# Balanbot-v2_0.net
KiCad netlist of a schematic drawn in EAGLE
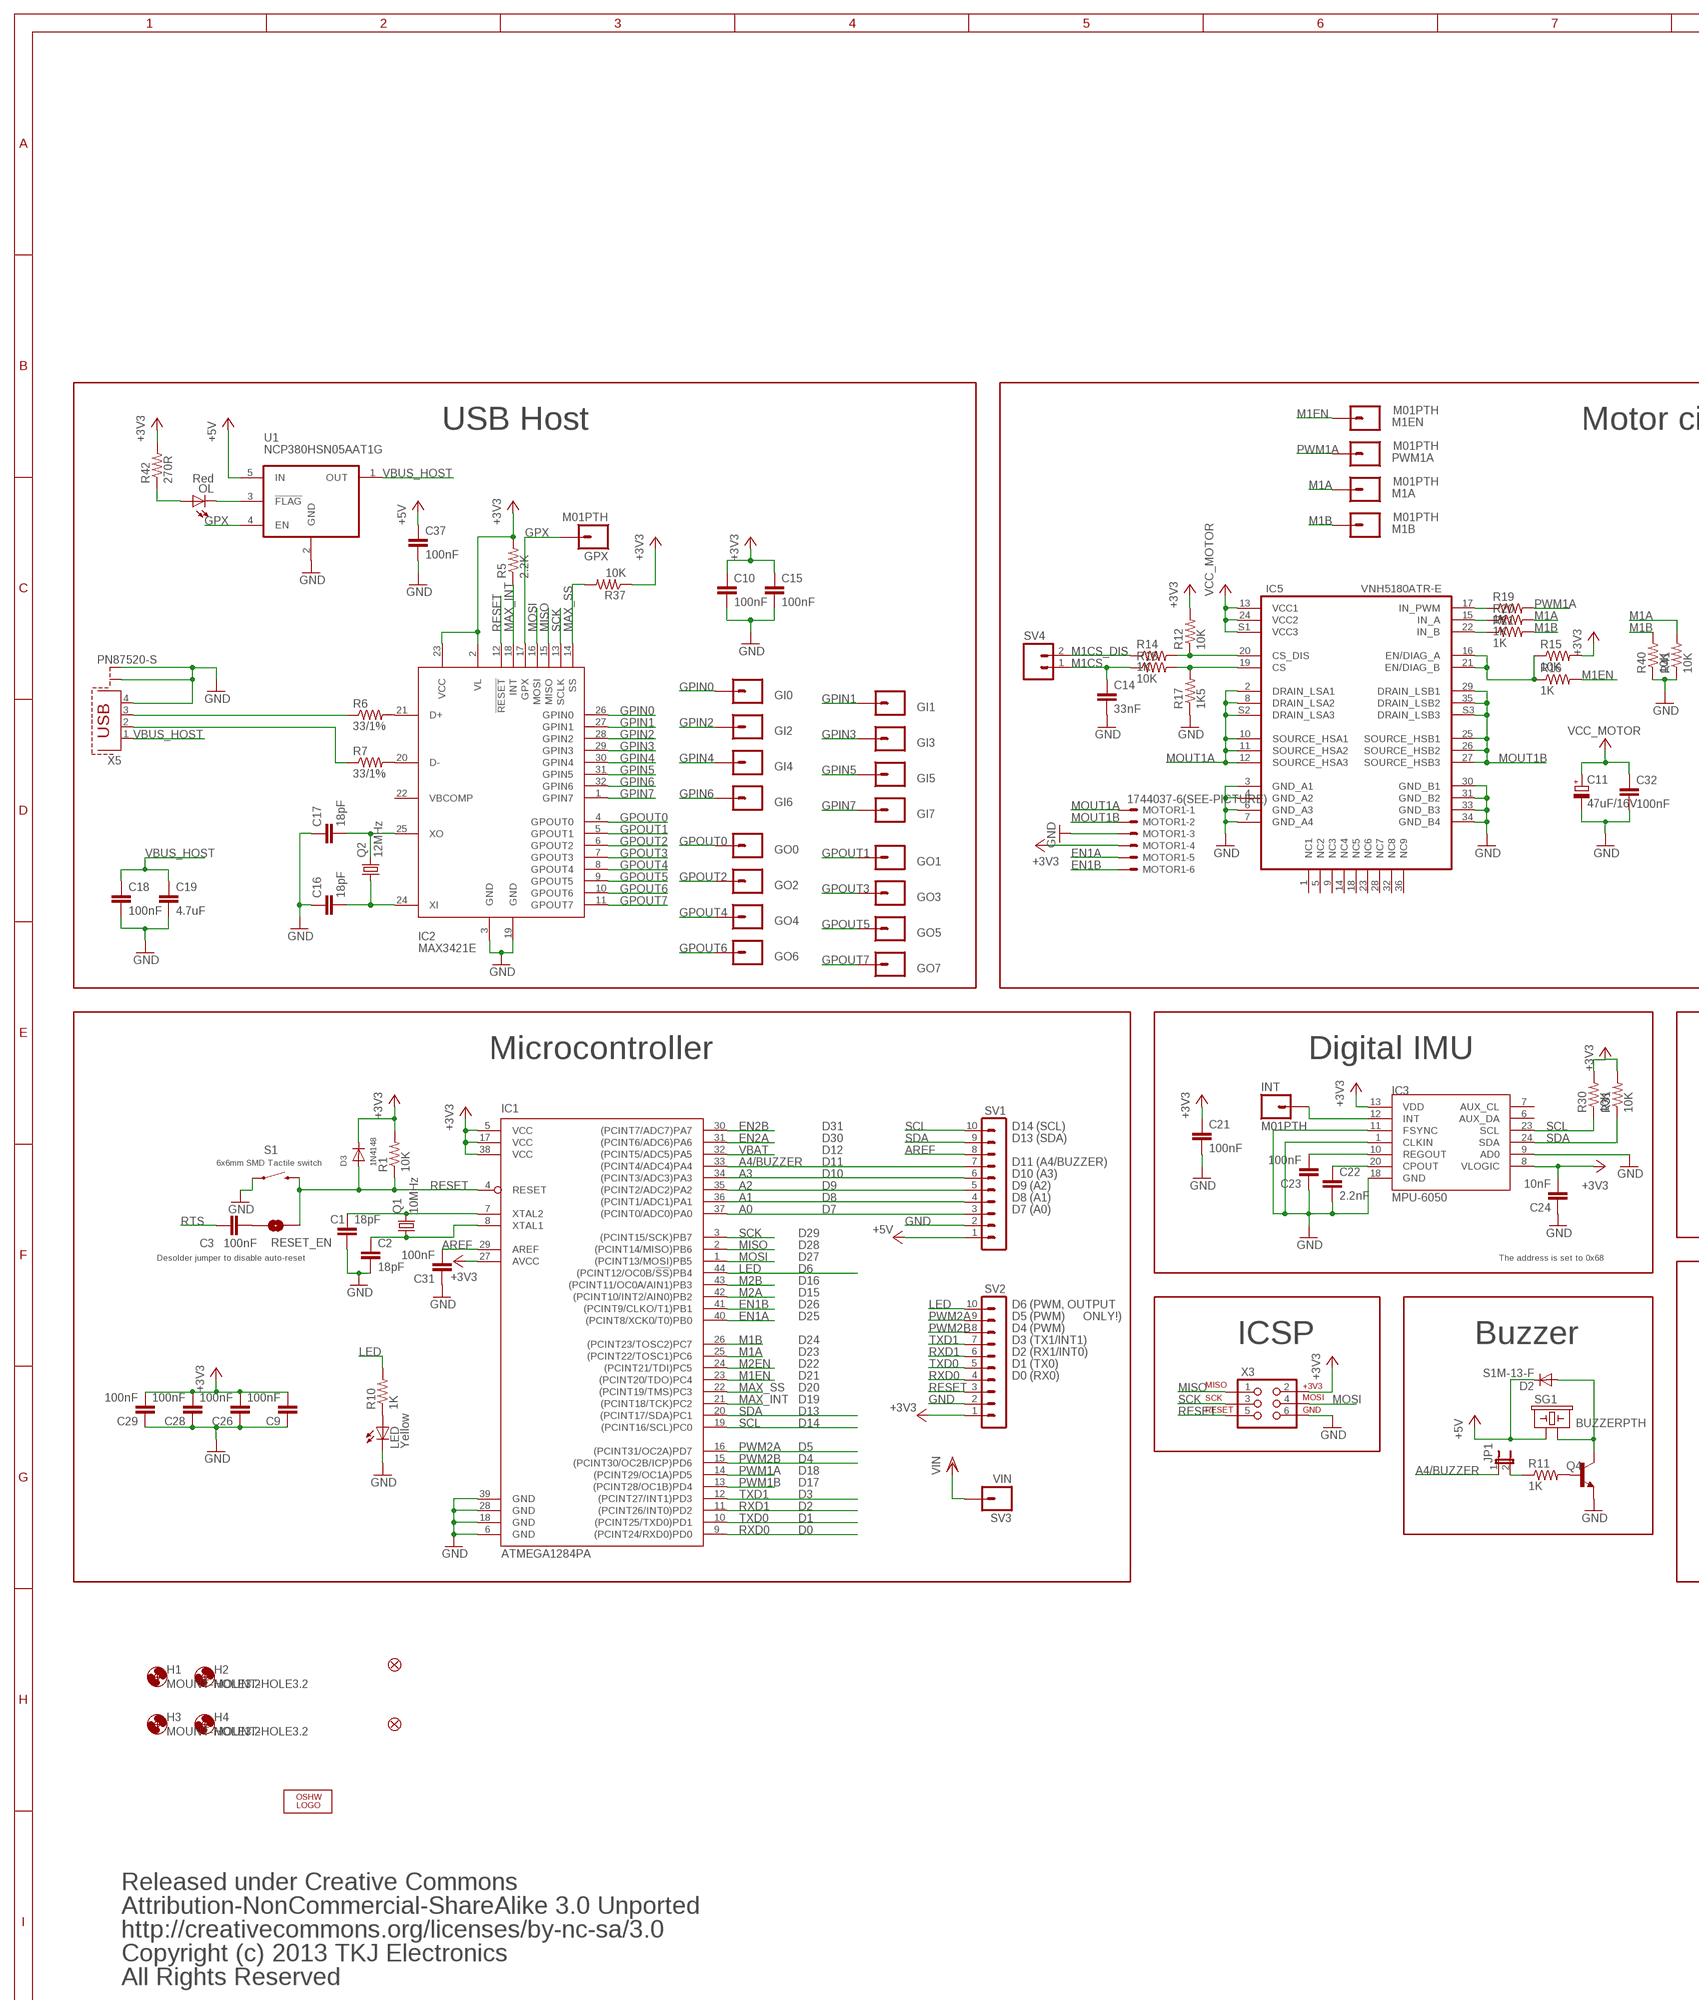
[diagram p0: schematic, sheet 1, part 1 of 2]
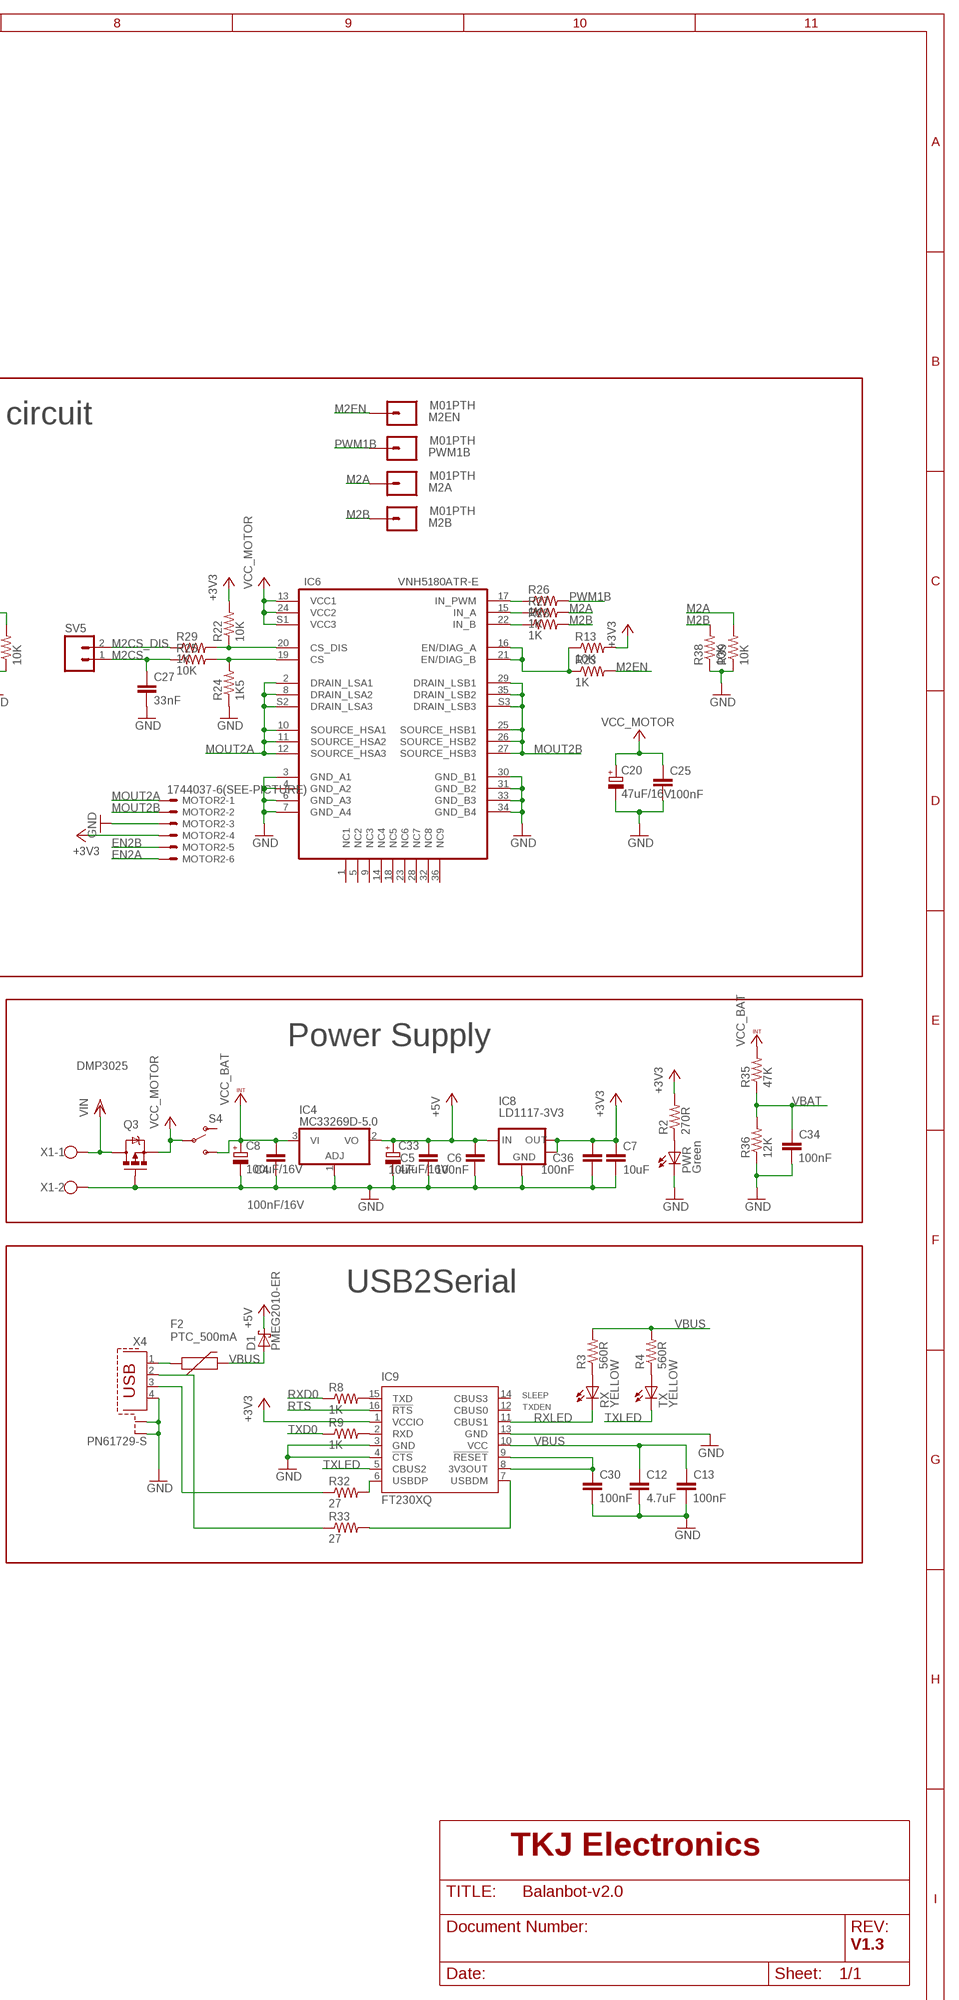
[diagram p1: schematic, sheet 1, part 2 of 2]

(export (version "E")
  (design (tool "Eeschema 10.0.6"))
  (components
    (comp (ref "C1")
      (value "18pF")
      (footprint "eagle-import:C0603")
      (libsource (lib "eagle-import") (part "C-EUC0603"))
    )
    (comp (ref "C2")
      (value "18pF")
      (footprint "eagle-import:C0603")
      (libsource (lib "eagle-import") (part "C-EUC0603"))
    )
    (comp (ref "C3")
      (value "100nF")
      (footprint "eagle-import:C0603")
      (libsource (lib "eagle-import") (part "C-EUC0603"))
    )
    (comp (ref "C4")
      (value "100nF/16V")
      (footprint "eagle-import:C0603")
      (libsource (lib "eagle-import") (part "C-EUC0603"))
    )
    (comp (ref "C5")
      (value "10uF")
      (footprint "eagle-import:C0805")
      (libsource (lib "eagle-import") (part "C-EUC0805"))
    )
    (comp (ref "C6")
      (value "100nF")
      (footprint "eagle-import:C0603")
      (libsource (lib "eagle-import") (part "C-EUC0603"))
    )
    (comp (ref "C7")
      (value "10uF")
      (footprint "eagle-import:C0805")
      (libsource (lib "eagle-import") (part "C-EUC0805"))
    )
    (comp (ref "C8")
      (value "100uF/16V")
      (footprint "eagle-import:PANASONIC_D")
      (libsource (lib "eagle-import") (part "CPOL-EUD"))
    )
    (comp (ref "C9")
      (value "100nF")
      (footprint "eagle-import:C0603")
      (libsource (lib "eagle-import") (part "C-EUC0603"))
    )
    (comp (ref "C10")
      (value "100nF")
      (footprint "eagle-import:C0603")
      (libsource (lib "eagle-import") (part "C-EUC0603"))
    )
    (comp (ref "C11")
      (value "47uF/16V")
      (footprint "eagle-import:PANASONIC_C")
      (libsource (lib "eagle-import") (part "CPOL-EUC"))
    )
    (comp (ref "C12")
      (value "4.7uF")
      (footprint "eagle-import:C0805")
      (libsource (lib "eagle-import") (part "C-EUC0805"))
    )
    (comp (ref "C13")
      (value "100nF")
      (footprint "eagle-import:C0603")
      (libsource (lib "eagle-import") (part "C-EUC0603"))
    )
    (comp (ref "C14")
      (value "33nF")
      (footprint "eagle-import:C0603")
      (libsource (lib "eagle-import") (part "C-EUC0603"))
    )
    (comp (ref "C15")
      (value "100nF")
      (footprint "eagle-import:C0603")
      (libsource (lib "eagle-import") (part "C-EUC0603"))
    )
    (comp (ref "C16")
      (value "18pF")
      (footprint "eagle-import:C0603")
      (libsource (lib "eagle-import") (part "C-EUC0603"))
    )
    (comp (ref "C17")
      (value "18pF")
      (footprint "eagle-import:C0603")
      (libsource (lib "eagle-import") (part "C-EUC0603"))
    )
    (comp (ref "C18")
      (value "100nF")
      (footprint "eagle-import:C0603")
      (libsource (lib "eagle-import") (part "C-EUC0603"))
    )
    (comp (ref "C19")
      (value "4.7uF")
      (footprint "eagle-import:C0805")
      (libsource (lib "eagle-import") (part "C-EUC0805"))
    )
    (comp (ref "C20")
      (value "47uF/16V")
      (footprint "eagle-import:PANASONIC_C")
      (libsource (lib "eagle-import") (part "CPOL-EUC"))
    )
    (comp (ref "C21")
      (value "100nF")
      (footprint "eagle-import:C0603")
      (libsource (lib "eagle-import") (part "C-EUC0603"))
    )
    (comp (ref "C22")
      (value "2.2nF")
      (footprint "eagle-import:C0603")
      (libsource (lib "eagle-import") (part "C-EUC0603"))
    )
    (comp (ref "C23")
      (value "100nF")
      (footprint "eagle-import:C0603")
      (libsource (lib "eagle-import") (part "C-EUC0603"))
    )
    (comp (ref "C24")
      (value "10nF")
      (footprint "eagle-import:C0603")
      (libsource (lib "eagle-import") (part "C-EUC0603"))
    )
    (comp (ref "C25")
      (value "100nF")
      (footprint "eagle-import:C0603")
      (libsource (lib "eagle-import") (part "C-EUC0603"))
    )
    (comp (ref "C26")
      (value "100nF")
      (footprint "eagle-import:C0603")
      (libsource (lib "eagle-import") (part "C-EUC0603"))
    )
    (comp (ref "C27")
      (value "33nF")
      (footprint "eagle-import:C0603")
      (libsource (lib "eagle-import") (part "C-EUC0603"))
    )
    (comp (ref "C28")
      (value "100nF")
      (footprint "eagle-import:C0603")
      (libsource (lib "eagle-import") (part "C-EUC0603"))
    )
    (comp (ref "C29")
      (value "100nF")
      (footprint "eagle-import:C0603")
      (libsource (lib "eagle-import") (part "C-EUC0603"))
    )
    (comp (ref "C30")
      (value "100nF")
      (footprint "eagle-import:C0603")
      (libsource (lib "eagle-import") (part "C-EUC0603"))
    )
    (comp (ref "C31")
      (value "100nF")
      (footprint "eagle-import:C0603")
      (libsource (lib "eagle-import") (part "C-EUC0603"))
    )
    (comp (ref "C32")
      (value "100nF")
      (footprint "eagle-import:C0603")
      (libsource (lib "eagle-import") (part "C-EUC0603"))
    )
    (comp (ref "C33")
      (value "47uF/16V")
      (footprint "eagle-import:PANASONIC_C")
      (libsource (lib "eagle-import") (part "CPOL-EUC"))
    )
    (comp (ref "C34")
      (value "100nF")
      (footprint "eagle-import:C0603")
      (libsource (lib "eagle-import") (part "C-EUC0603"))
    )
    (comp (ref "C36")
      (value "100nF")
      (footprint "eagle-import:C0603")
      (libsource (lib "eagle-import") (part "C-EUC0603"))
    )
    (comp (ref "C37")
      (value "100nF")
      (footprint "eagle-import:C0603")
      (libsource (lib "eagle-import") (part "C-EUC0603"))
    )
    (comp (ref "D1")
      (value "PMEG2010-ER")
      (footprint "eagle-import:SOD123")
      (libsource (lib "eagle-import") (part "PMEG2010-ER"))
    )
    (comp (ref "D2")
      (value "S1M-13-F")
      (footprint "eagle-import:DO214AC")
      (libsource (lib "eagle-import") (part "S1M-13-F"))
    )
    (comp (ref "D3")
      (value "1N4148")
      (footprint "eagle-import:SOD-523")
      (libsource (lib "eagle-import") (part "DIODESOD-523"))
    )
    (comp (ref "F2")
      (value "PTC_500mA")
      (footprint "eagle-import:PTC-1206")
      (libsource (lib "eagle-import") (part "PTCSMD"))
    )
    (comp (ref "GI0")
      (value "M01PTH")
      (footprint "eagle-import:1X01")
      (libsource (lib "eagle-import") (part "M01PTH"))
    )
    (comp (ref "GI1")
      (value "M01PTH")
      (footprint "eagle-import:1X01")
      (libsource (lib "eagle-import") (part "M01PTH"))
    )
    (comp (ref "GI2")
      (value "M01PTH")
      (footprint "eagle-import:1X01")
      (libsource (lib "eagle-import") (part "M01PTH"))
    )
    (comp (ref "GI3")
      (value "M01PTH")
      (footprint "eagle-import:1X01")
      (libsource (lib "eagle-import") (part "M01PTH"))
    )
    (comp (ref "GI4")
      (value "M01PTH")
      (footprint "eagle-import:1X01")
      (libsource (lib "eagle-import") (part "M01PTH"))
    )
    (comp (ref "GI5")
      (value "M01PTH")
      (footprint "eagle-import:1X01")
      (libsource (lib "eagle-import") (part "M01PTH"))
    )
    (comp (ref "GI6")
      (value "M01PTH")
      (footprint "eagle-import:1X01")
      (libsource (lib "eagle-import") (part "M01PTH"))
    )
    (comp (ref "GI7")
      (value "M01PTH")
      (footprint "eagle-import:1X01")
      (libsource (lib "eagle-import") (part "M01PTH"))
    )
    (comp (ref "GO0")
      (value "M01PTH")
      (footprint "eagle-import:1X01")
      (libsource (lib "eagle-import") (part "M01PTH"))
    )
    (comp (ref "GO1")
      (value "M01PTH")
      (footprint "eagle-import:1X01")
      (libsource (lib "eagle-import") (part "M01PTH"))
    )
    (comp (ref "GO2")
      (value "M01PTH")
      (footprint "eagle-import:1X01")
      (libsource (lib "eagle-import") (part "M01PTH"))
    )
    (comp (ref "GO3")
      (value "M01PTH")
      (footprint "eagle-import:1X01")
      (libsource (lib "eagle-import") (part "M01PTH"))
    )
    (comp (ref "GO4")
      (value "M01PTH")
      (footprint "eagle-import:1X01")
      (libsource (lib "eagle-import") (part "M01PTH"))
    )
    (comp (ref "GO5")
      (value "M01PTH")
      (footprint "eagle-import:1X01")
      (libsource (lib "eagle-import") (part "M01PTH"))
    )
    (comp (ref "GO6")
      (value "M01PTH")
      (footprint "eagle-import:1X01")
      (libsource (lib "eagle-import") (part "M01PTH"))
    )
    (comp (ref "GO7")
      (value "M01PTH")
      (footprint "eagle-import:1X01")
      (libsource (lib "eagle-import") (part "M01PTH"))
    )
    (comp (ref "GPX")
      (value "M01PTH")
      (footprint "eagle-import:1X01")
      (libsource (lib "eagle-import") (part "M01PTH"))
    )
    (comp (ref "H1")
      (value "MOUNT-HOLE3.2")
      (footprint "eagle-import:3,2")
      (libsource (lib "eagle-import") (part "MOUNT-HOLE3.2"))
    )
    (comp (ref "H2")
      (value "MOUNT-HOLE3.2")
      (footprint "eagle-import:3,2")
      (libsource (lib "eagle-import") (part "MOUNT-HOLE3.2"))
    )
    (comp (ref "H3")
      (value "MOUNT-HOLE3.2")
      (footprint "eagle-import:3,2")
      (libsource (lib "eagle-import") (part "MOUNT-HOLE3.2"))
    )
    (comp (ref "H4")
      (value "MOUNT-HOLE3.2")
      (footprint "eagle-import:3,2")
      (libsource (lib "eagle-import") (part "MOUNT-HOLE3.2"))
    )
    (comp (ref "IC1")
      (value "ATMEGA1284PA")
      (footprint "eagle-import:TQFP44")
      (fields (field (name "MPN") "ATMEGA1284P-10AU"))
      (libsource (lib "eagle-import") (part "ATMEGA1284PA"))
    )
    (comp (ref "IC2")
      (value "MAX3421E")
      (footprint "eagle-import:TQFP32_8MIL")
      (libsource (lib "eagle-import") (part "MAX3421E"))
    )
    (comp (ref "IC3")
      (value "MPU-6050")
      (footprint "eagle-import:TESTING_QFN-24-4MM2")
      (libsource (lib "eagle-import") (part "TESTING_MPU-6050-1"))
    )
    (comp (ref "IC4")
      (value "MC33269D-5.0")
      (footprint "eagle-import:DPACK")
      (libsource (lib "eagle-import") (part "MC33269?D"))
    )
    (comp (ref "IC5")
      (value "VNH5180ATR-E")
      (footprint "eagle-import:POWERSSO-36")
      (libsource (lib "eagle-import") (part "VNH5180ATR-E"))
    )
    (comp (ref "IC6")
      (value "VNH5180ATR-E")
      (footprint "eagle-import:POWERSSO-36")
      (libsource (lib "eagle-import") (part "VNH5180ATR-E"))
    )
    (comp (ref "IC8")
      (value "LD1117-3V3")
      (footprint "eagle-import:SOT223")
      (libsource (lib "eagle-import") (part "LM1117-SOT223"))
    )
    (comp (ref "IC9")
      (value "FT230XQ")
      (footprint "eagle-import:QFN16")
      (libsource (lib "eagle-import") (part "FT230XQ"))
    )
    (comp (ref "INT")
      (value "M01PTH")
      (footprint "eagle-import:1X01")
      (libsource (lib "eagle-import") (part "M01PTH"))
    )
    (comp (ref "JP1")
      (value "JP1E")
      (footprint "eagle-import:JP1")
      (libsource (lib "eagle-import") (part "JP1E"))
    )
    (comp (ref "JP2")
      (value "FIDUCIALUFIDUCIAL")
      (footprint "eagle-import:MICRO-FIDUCIAL")
      (libsource (lib "eagle-import") (part "FIDUCIALUFIDUCIAL"))
    )
    (comp (ref "JP3")
      (value "FIDUCIAL1X2")
      (footprint "eagle-import:FIDUCIAL-1X2")
      (libsource (lib "eagle-import") (part "FIDUCIAL1X2"))
    )
    (comp (ref "LED")
      (value "Yellow")
      (footprint "eagle-import:CHIPLED_0805")
      (libsource (lib "eagle-import") (part "LEDCHIPLED_0805"))
    )
    (comp (ref "LOGO2")
      (value "OSHW_LOGO_FILLX0200-NT")
      (footprint "eagle-import:OSHW_FILLX200_NOTEXT")
      (libsource (lib "eagle-import") (part "OSHW_LOGO_FILLX0200-NT"))
    )
    (comp (ref "M1A")
      (value "M01PTH")
      (footprint "eagle-import:1X01")
      (libsource (lib "eagle-import") (part "M01PTH"))
    )
    (comp (ref "M1B")
      (value "M01PTH")
      (footprint "eagle-import:1X01")
      (libsource (lib "eagle-import") (part "M01PTH"))
    )
    (comp (ref "M1EN")
      (value "M01PTH")
      (footprint "eagle-import:1X01")
      (libsource (lib "eagle-import") (part "M01PTH"))
    )
    (comp (ref "M2A")
      (value "M01PTH")
      (footprint "eagle-import:1X01")
      (libsource (lib "eagle-import") (part "M01PTH"))
    )
    (comp (ref "M2B")
      (value "M01PTH")
      (footprint "eagle-import:1X01")
      (libsource (lib "eagle-import") (part "M01PTH"))
    )
    (comp (ref "M2EN")
      (value "M01PTH")
      (footprint "eagle-import:1X01")
      (libsource (lib "eagle-import") (part "M01PTH"))
    )
    (comp (ref "MOTOR1")
      (value "1744037-6(SEE-PICTURE)")
      (footprint "eagle-import:22-23-2061")
      (fields (field (name "MF") "MOLEX") (field (name "MPN") "22-23-2061"))
      (libsource (lib "eagle-import") (part "22-23-2061"))
    )
    (comp (ref "MOTOR2")
      (value "1744037-6(SEE-PICTURE)")
      (footprint "eagle-import:22-23-2061")
      (fields (field (name "MF") "MOLEX") (field (name "MPN") "22-23-2061"))
      (libsource (lib "eagle-import") (part "22-23-2061"))
    )
    (comp (ref "OL")
      (value "Red")
      (footprint "eagle-import:CHIPLED_0805")
      (libsource (lib "eagle-import") (part "LEDCHIPLED_0805"))
    )
    (comp (ref "PWM1A")
      (value "M01PTH")
      (footprint "eagle-import:1X01")
      (libsource (lib "eagle-import") (part "M01PTH"))
    )
    (comp (ref "PWM1B")
      (value "M01PTH")
      (footprint "eagle-import:1X01")
      (libsource (lib "eagle-import") (part "M01PTH"))
    )
    (comp (ref "PWR")
      (value "Green")
      (footprint "eagle-import:CHIPLED_0805")
      (libsource (lib "eagle-import") (part "LEDCHIPLED_0805"))
    )
    (comp (ref "Q1")
      (value "10MHz")
      (footprint "eagle-import:HC49UP")
      (libsource (lib "eagle-import") (part "CRYSTALHC49UP"))
    )
    (comp (ref "Q2")
      (value "12MHz")
      (footprint "eagle-import:HC49UP")
      (libsource (lib "eagle-import") (part "CRYSTALHC49UP"))
    )
    (comp (ref "Q3")
      (value "DMP3025")
      (footprint "eagle-import:DPAK")
      (libsource (lib "eagle-import") (part "MOSFET-PCHANNEL"))
    )
    (comp (ref "Q4")
      (value "TRANSISTOR_NPNSOT23-3")
      (footprint "eagle-import:SOT23-3")
      (libsource (lib "eagle-import") (part "TRANSISTOR_NPNSOT23-3"))
    )
    (comp (ref "R1")
      (value "10K")
      (footprint "eagle-import:R0603")
      (libsource (lib "eagle-import") (part "R-US_R0603"))
    )
    (comp (ref "R2")
      (value "270R")
      (footprint "eagle-import:R0603")
      (libsource (lib "eagle-import") (part "R-US_R0603"))
    )
    (comp (ref "R3")
      (value "560R")
      (footprint "eagle-import:R0603")
      (libsource (lib "eagle-import") (part "R-US_R0603"))
    )
    (comp (ref "R4")
      (value "560R")
      (footprint "eagle-import:R0603")
      (libsource (lib "eagle-import") (part "R-US_R0603"))
    )
    (comp (ref "R5")
      (value "2.2K")
      (footprint "eagle-import:R0603")
      (libsource (lib "eagle-import") (part "R-US_R0603"))
    )
    (comp (ref "R6")
      (value "33/1%")
      (footprint "eagle-import:R0603")
      (libsource (lib "eagle-import") (part "R-US_R0603"))
    )
    (comp (ref "R7")
      (value "33/1%")
      (footprint "eagle-import:R0603")
      (libsource (lib "eagle-import") (part "R-US_R0603"))
    )
    (comp (ref "R8")
      (value "1K")
      (footprint "eagle-import:R0603")
      (libsource (lib "eagle-import") (part "R-US_R0603"))
    )
    (comp (ref "R9")
      (value "1K")
      (footprint "eagle-import:R0603")
      (libsource (lib "eagle-import") (part "R-US_R0603"))
    )
    (comp (ref "R10")
      (value "1K")
      (footprint "eagle-import:R0603")
      (libsource (lib "eagle-import") (part "R-US_R0603"))
    )
    (comp (ref "R11")
      (value "1K")
      (footprint "eagle-import:R0603")
      (libsource (lib "eagle-import") (part "R-US_R0603"))
    )
    (comp (ref "R12")
      (value "10K")
      (footprint "eagle-import:R0603")
      (libsource (lib "eagle-import") (part "R-US_R0603"))
    )
    (comp (ref "R13")
      (value "10K")
      (footprint "eagle-import:R0603")
      (libsource (lib "eagle-import") (part "R-US_R0603"))
    )
    (comp (ref "R14")
      (value "1K")
      (footprint "eagle-import:R0603")
      (libsource (lib "eagle-import") (part "R-US_R0603"))
    )
    (comp (ref "R15")
      (value "10K")
      (footprint "eagle-import:R0603")
      (libsource (lib "eagle-import") (part "R-US_R0603"))
    )
    (comp (ref "R16")
      (value "1K")
      (footprint "eagle-import:R0603")
      (libsource (lib "eagle-import") (part "R-US_R0603"))
    )
    (comp (ref "R17")
      (value "1K5")
      (footprint "eagle-import:R0603")
      (libsource (lib "eagle-import") (part "R-US_R0603"))
    )
    (comp (ref "R18")
      (value "10K")
      (footprint "eagle-import:R0603")
      (libsource (lib "eagle-import") (part "R-US_R0603"))
    )
    (comp (ref "R19")
      (value "1K")
      (footprint "eagle-import:R0603")
      (libsource (lib "eagle-import") (part "R-US_R0603"))
    )
    (comp (ref "R20")
      (value "1K")
      (footprint "eagle-import:R0603")
      (libsource (lib "eagle-import") (part "R-US_R0603"))
    )
    (comp (ref "R21")
      (value "1K")
      (footprint "eagle-import:R0603")
      (libsource (lib "eagle-import") (part "R-US_R0603"))
    )
    (comp (ref "R22")
      (value "10K")
      (footprint "eagle-import:R0603")
      (libsource (lib "eagle-import") (part "R-US_R0603"))
    )
    (comp (ref "R23")
      (value "1K")
      (footprint "eagle-import:R0603")
      (libsource (lib "eagle-import") (part "R-US_R0603"))
    )
    (comp (ref "R24")
      (value "1K5")
      (footprint "eagle-import:R0603")
      (libsource (lib "eagle-import") (part "R-US_R0603"))
    )
    (comp (ref "R25")
      (value "10K")
      (footprint "eagle-import:R0603")
      (libsource (lib "eagle-import") (part "R-US_R0603"))
    )
    (comp (ref "R26")
      (value "1K")
      (footprint "eagle-import:R0603")
      (libsource (lib "eagle-import") (part "R-US_R0603"))
    )
    (comp (ref "R27")
      (value "1K")
      (footprint "eagle-import:R0603")
      (libsource (lib "eagle-import") (part "R-US_R0603"))
    )
    (comp (ref "R28")
      (value "1K")
      (footprint "eagle-import:R0603")
      (libsource (lib "eagle-import") (part "R-US_R0603"))
    )
    (comp (ref "R29")
      (value "1K")
      (footprint "eagle-import:R0603")
      (libsource (lib "eagle-import") (part "R-US_R0603"))
    )
    (comp (ref "R30")
      (value "10K")
      (footprint "eagle-import:R0603")
      (libsource (lib "eagle-import") (part "R-US_R0603"))
    )
    (comp (ref "R31")
      (value "10K")
      (footprint "eagle-import:R0603")
      (libsource (lib "eagle-import") (part "R-US_R0603"))
    )
    (comp (ref "R32")
      (value "27")
      (footprint "eagle-import:R0603")
      (libsource (lib "eagle-import") (part "R-US_R0603"))
    )
    (comp (ref "R33")
      (value "27")
      (footprint "eagle-import:R0603")
      (libsource (lib "eagle-import") (part "R-US_R0603"))
    )
    (comp (ref "R35")
      (value "47K")
      (footprint "eagle-import:R0603")
      (libsource (lib "eagle-import") (part "R-US_R0603"))
    )
    (comp (ref "R36")
      (value "12K")
      (footprint "eagle-import:R0603")
      (libsource (lib "eagle-import") (part "R-US_R0603"))
    )
    (comp (ref "R37")
      (value "10K")
      (footprint "eagle-import:R0603")
      (libsource (lib "eagle-import") (part "R-US_R0603"))
    )
    (comp (ref "R38")
      (value "10K")
      (footprint "eagle-import:R0603")
      (libsource (lib "eagle-import") (part "R-US_R0603"))
    )
    (comp (ref "R39")
      (value "10K")
      (footprint "eagle-import:R0603")
      (libsource (lib "eagle-import") (part "R-US_R0603"))
    )
    (comp (ref "R40")
      (value "10K")
      (footprint "eagle-import:R0603")
      (libsource (lib "eagle-import") (part "R-US_R0603"))
    )
    (comp (ref "R41")
      (value "10K")
      (footprint "eagle-import:R0603")
      (libsource (lib "eagle-import") (part "R-US_R0603"))
    )
    (comp (ref "R42")
      (value "270R")
      (footprint "eagle-import:R0603")
      (libsource (lib "eagle-import") (part "R-US_R0603"))
    )
    (comp (ref "RESET_EN")
      (value "SOLDERJUMPERNC")
      (footprint "eagle-import:SJ_2S")
      (libsource (lib "eagle-import") (part "SOLDERJUMPERNC"))
    )
    (comp (ref "RX")
      (value "YELLOW")
      (footprint "eagle-import:CHIPLED_0805")
      (libsource (lib "eagle-import") (part "LEDCHIPLED_0805"))
    )
    (comp (ref "S1")
      (value "DTSM-62K-S-V-T/R(SN431)")
      (footprint "eagle-import:TACTILE_SWITCH_TALL")
      (libsource (lib "eagle-import") (part "SWITCH-MOMENTARY-2"))
    )
    (comp (ref "S4")
      (value "SWITCH-SPDTML")
      (footprint "eagle-import:SWITCH-SPDT")
      (libsource (lib "eagle-import") (part "SWITCH-SPDTML"))
    )
    (comp (ref "SG1")
      (value "BUZZERPTH")
      (footprint "eagle-import:BUZZER-12MM")
      (libsource (lib "eagle-import") (part "BUZZERPTH"))
    )
    (comp (ref "SV1")
      (value "MA10-1")
      (footprint "eagle-import:MA10-1")
      (libsource (lib "eagle-import") (part "MA10-1"))
    )
    (comp (ref "SV2")
      (value "MA10-1")
      (footprint "eagle-import:MA10-1")
      (libsource (lib "eagle-import") (part "MA10-1"))
    )
    (comp (ref "SV3")
      (value "VIN")
      (footprint "eagle-import:1X01")
      (libsource (lib "eagle-import") (part "M01PTH"))
    )
    (comp (ref "SV4")
      (value "M02PTH")
      (footprint "eagle-import:1X02")
      (libsource (lib "eagle-import") (part "M02PTH"))
    )
    (comp (ref "SV5")
      (value "M02PTH")
      (footprint "eagle-import:1X02")
      (libsource (lib "eagle-import") (part "M02PTH"))
    )
    (comp (ref "TX")
      (value "YELLOW")
      (footprint "eagle-import:CHIPLED_0805")
      (libsource (lib "eagle-import") (part "LEDCHIPLED_0805"))
    )
    (comp (ref "U1")
      (value "NCP380HSN05AAT1G")
      (footprint "eagle-import:SOT23-5")
      (libsource (lib "eagle-import") (part "POWERSW_FIX-SOT5-1"))
    )
    (comp (ref "X1")
      (value "W237-102")
      (footprint "eagle-import:W237-102")
      (fields (field (name "MPN") "237-102"))
      (libsource (lib "eagle-import") (part "W237-102"))
    )
    (comp (ref "X3")
      (value "AVR_SPI_PRG_62X3_LOCK")
      (footprint "eagle-import:2X3_LOCK")
      (libsource (lib "eagle-import") (part "AVR_SPI_PRG_62X3_LOCK"))
    )
    (comp (ref "X4")
      (value "PN61729-S")
      (footprint "eagle-import:PN61729-S")
      (libsource (lib "eagle-import") (part "PN61729-S"))
    )
    (comp (ref "X5")
      (value "PN87520-S")
      (footprint "eagle-import:PN87520-S")
      (libsource (lib "eagle-import") (part "PN87520-S"))
    )
  )
  (nets
    (net (code "1") (name "+3V3") (class "Default")
      (node (ref "C10") (pin "1") (pinfunction "1_1") (pintype "passive"))
      (node (ref "C15") (pin "1") (pinfunction "1_1") (pintype "passive"))
      (node (ref "C21") (pin "1") (pinfunction "1_1") (pintype "passive"))
      (node (ref "C24") (pin "2") (pinfunction "2_2") (pintype "passive"))
      (node (ref "C26") (pin "2") (pinfunction "2_2") (pintype "passive"))
      (node (ref "C28") (pin "2") (pinfunction "2_2") (pintype "passive"))
      (node (ref "C29") (pin "2") (pinfunction "2_2") (pintype "passive"))
      (node (ref "C36") (pin "2") (pinfunction "2_2") (pintype "passive"))
      (node (ref "C7") (pin "1") (pinfunction "1_1") (pintype "passive"))
      (node (ref "C9") (pin "2") (pinfunction "2_2") (pintype "passive"))
      (node (ref "D3") (pin "K") (pinfunction "C_K") (pintype "passive"))
      (node (ref "IC1") (pin "17") (pinfunction "VCC_17") (pintype "power_in"))
      (node (ref "IC1") (pin "27") (pinfunction "AVCC_27") (pintype "power_in"))
      (node (ref "IC1") (pin "38") (pinfunction "VCC_38") (pintype "power_in"))
      (node (ref "IC1") (pin "5") (pinfunction "VCC_5") (pintype "power_in"))
      (node (ref "IC2") (pin "2") (pinfunction "VL_2") (pintype "input"))
      (node (ref "IC2") (pin "23") (pinfunction "VCC_23") (pintype "power_in"))
      (node (ref "IC3") (pin "13") (pinfunction "VDD_13") (pintype "bidirectional"))
      (node (ref "IC3") (pin "8") (pinfunction "VLOGIC_8") (pintype "bidirectional"))
      (node (ref "IC8") (pin "2") (pinfunction "OUT_2") (pintype "output"))
      (node (ref "IC8") (pin "4") (pinfunction "OUT_4") (pintype "output"))
      (node (ref "IC9") (pin "1") (pinfunction "VCCIO_1") (pintype "power_in"))
      (node (ref "MOTOR1") (pin "4") (pinfunction "S_4") (pintype "passive"))
      (node (ref "MOTOR2") (pin "4") (pinfunction "S_4") (pintype "passive"))
      (node (ref "R1") (pin "2") (pinfunction "2_2") (pintype "passive"))
      (node (ref "R12") (pin "2") (pinfunction "2_2") (pintype "passive"))
      (node (ref "R13") (pin "2") (pinfunction "2_2") (pintype "passive"))
      (node (ref "R15") (pin "2") (pinfunction "2_2") (pintype "passive"))
      (node (ref "R2") (pin "2") (pinfunction "2_2") (pintype "passive"))
      (node (ref "R22") (pin "2") (pinfunction "2_2") (pintype "passive"))
      (node (ref "R30") (pin "2") (pinfunction "2_2") (pintype "passive"))
      (node (ref "R31") (pin "2") (pinfunction "2_2") (pintype "passive"))
      (node (ref "R37") (pin "1") (pinfunction "1_1") (pintype "passive"))
      (node (ref "R42") (pin "2") (pinfunction "2_2") (pintype "passive"))
      (node (ref "R5") (pin "2") (pinfunction "2_2") (pintype "passive"))
      (node (ref "SV2") (pin "1") (pinfunction "1_1") (pintype "passive"))
      (node (ref "X3") (pin "2") (pinfunction "2_2") (pintype "passive"))
    )
    (net (code "2") (name "+5V") (class "Default")
      (node (ref "C33") (pin "+") (pinfunction "+_+") (pintype "passive"))
      (node (ref "C37") (pin "1") (pinfunction "1_1") (pintype "passive"))
      (node (ref "C5") (pin "1") (pinfunction "1_1") (pintype "passive"))
      (node (ref "C6") (pin "2") (pinfunction "2_2") (pintype "passive"))
      (node (ref "D1") (pin "C") (pinfunction "C_C") (pintype "passive"))
      (node (ref "D2") (pin "C") (pinfunction "C_C") (pintype "passive"))
      (node (ref "IC4") (pin "2") (pinfunction "VO_2") (pintype "passive"))
      (node (ref "IC8") (pin "3") (pinfunction "IN_3") (pintype "input"))
      (node (ref "SG1") (pin "+") (pinfunction "1_+") (pintype "passive"))
      (node (ref "SV1") (pin "1") (pinfunction "1_1") (pintype "passive"))
      (node (ref "U1") (pin "5") (pinfunction "IN_5") (pintype "bidirectional"))
    )
    (net (code "3") (name "/A0") (class "Default")
      (node (ref "IC1") (pin "37") (pinfunction "(PCINT0/ADC0)PA0_37") (pintype "bidirectional"))
      (node (ref "SV1") (pin "3") (pinfunction "3_3") (pintype "passive"))
    )
    (net (code "4") (name "/A1") (class "Default")
      (node (ref "IC1") (pin "36") (pinfunction "(PCINT1/ADC1)PA1_36") (pintype "bidirectional"))
      (node (ref "SV1") (pin "4") (pinfunction "4_4") (pintype "passive"))
    )
    (net (code "5") (name "/A2") (class "Default")
      (node (ref "IC1") (pin "35") (pinfunction "(PCINT2/ADC2)PA2_35") (pintype "bidirectional"))
      (node (ref "SV1") (pin "5") (pinfunction "5_5") (pintype "passive"))
    )
    (net (code "6") (name "/A3") (class "Default")
      (node (ref "IC1") (pin "34") (pinfunction "(PCINT3/ADC3)PA3_34") (pintype "bidirectional"))
      (node (ref "SV1") (pin "6") (pinfunction "6_6") (pintype "passive"))
    )
    (net (code "7") (name "/A4{slash}BUZZER") (class "Default")
      (node (ref "IC1") (pin "33") (pinfunction "(PCINT4/ADC4)PA4_33") (pintype "bidirectional"))
      (node (ref "JP1") (pin "1") (pinfunction "1_1") (pintype "passive"))
      (node (ref "SV1") (pin "7") (pinfunction "7_7") (pintype "passive"))
    )
    (net (code "8") (name "/AREF") (class "Default")
      (node (ref "C31") (pin "2") (pinfunction "2_2") (pintype "passive"))
      (node (ref "IC1") (pin "29") (pinfunction "AREF_29") (pintype "passive"))
      (node (ref "SV1") (pin "8") (pinfunction "8_8") (pintype "passive"))
    )
    (net (code "9") (name "/EN1A") (class "Default")
      (node (ref "IC1") (pin "40") (pinfunction "(PCINT8/XCK0/T0)PB0_40") (pintype "bidirectional"))
      (node (ref "MOTOR1") (pin "5") (pinfunction "S_5") (pintype "passive"))
    )
    (net (code "10") (name "/EN1B") (class "Default")
      (node (ref "IC1") (pin "41") (pinfunction "(PCINT9/CLKO/T1)PB1_41") (pintype "bidirectional"))
      (node (ref "MOTOR1") (pin "6") (pinfunction "S_6") (pintype "passive"))
    )
    (net (code "11") (name "/EN2A") (class "Default")
      (node (ref "IC1") (pin "31") (pinfunction "(PCINT6/ADC6)PA6_31") (pintype "bidirectional"))
      (node (ref "MOTOR2") (pin "6") (pinfunction "S_6") (pintype "passive"))
    )
    (net (code "12") (name "/EN2B") (class "Default")
      (node (ref "IC1") (pin "30") (pinfunction "(PCINT7/ADC7)PA7_30") (pintype "bidirectional"))
      (node (ref "MOTOR2") (pin "5") (pinfunction "S_5") (pintype "passive"))
    )
    (net (code "13") (name "/GPIN0") (class "Default")
      (node (ref "GI0") (pin "1") (pinfunction "1_1") (pintype "passive"))
      (node (ref "IC2") (pin "26") (pinfunction "GPIN0_26") (pintype "input"))
    )
    (net (code "14") (name "/GPIN1") (class "Default")
      (node (ref "GI1") (pin "1") (pinfunction "1_1") (pintype "passive"))
      (node (ref "IC2") (pin "27") (pinfunction "GPIN1_27") (pintype "input"))
    )
    (net (code "15") (name "/GPIN2") (class "Default")
      (node (ref "GI2") (pin "1") (pinfunction "1_1") (pintype "passive"))
      (node (ref "IC2") (pin "28") (pinfunction "GPIN2_28") (pintype "input"))
    )
    (net (code "16") (name "/GPIN3") (class "Default")
      (node (ref "GI3") (pin "1") (pinfunction "1_1") (pintype "passive"))
      (node (ref "IC2") (pin "29") (pinfunction "GPIN3_29") (pintype "input"))
    )
    (net (code "17") (name "/GPIN4") (class "Default")
      (node (ref "GI4") (pin "1") (pinfunction "1_1") (pintype "passive"))
      (node (ref "IC2") (pin "30") (pinfunction "GPIN4_30") (pintype "input"))
    )
    (net (code "18") (name "/GPIN5") (class "Default")
      (node (ref "GI5") (pin "1") (pinfunction "1_1") (pintype "passive"))
      (node (ref "IC2") (pin "31") (pinfunction "GPIN5_31") (pintype "input"))
    )
    (net (code "19") (name "/GPIN6") (class "Default")
      (node (ref "GI6") (pin "1") (pinfunction "1_1") (pintype "passive"))
      (node (ref "IC2") (pin "32") (pinfunction "GPIN6_32") (pintype "input"))
    )
    (net (code "20") (name "/GPIN7") (class "Default")
      (node (ref "GI7") (pin "1") (pinfunction "1_1") (pintype "passive"))
      (node (ref "IC2") (pin "1") (pinfunction "GPIN7_1") (pintype "input"))
    )
    (net (code "21") (name "/GPOUT0") (class "Default")
      (node (ref "GO0") (pin "1") (pinfunction "1_1") (pintype "passive"))
      (node (ref "IC2") (pin "4") (pinfunction "GPOUT0_4") (pintype "output"))
    )
    (net (code "22") (name "/GPOUT1") (class "Default")
      (node (ref "GO1") (pin "1") (pinfunction "1_1") (pintype "passive"))
      (node (ref "IC2") (pin "5") (pinfunction "GPOUT1_5") (pintype "output"))
    )
    (net (code "23") (name "/GPOUT2") (class "Default")
      (node (ref "GO2") (pin "1") (pinfunction "1_1") (pintype "passive"))
      (node (ref "IC2") (pin "6") (pinfunction "GPOUT2_6") (pintype "output"))
    )
    (net (code "24") (name "/GPOUT3") (class "Default")
      (node (ref "GO3") (pin "1") (pinfunction "1_1") (pintype "passive"))
      (node (ref "IC2") (pin "7") (pinfunction "GPOUT3_7") (pintype "output"))
    )
    (net (code "25") (name "/GPOUT4") (class "Default")
      (node (ref "GO4") (pin "1") (pinfunction "1_1") (pintype "passive"))
      (node (ref "IC2") (pin "8") (pinfunction "GPOUT4_8") (pintype "output"))
    )
    (net (code "26") (name "/GPOUT5") (class "Default")
      (node (ref "GO5") (pin "1") (pinfunction "1_1") (pintype "passive"))
      (node (ref "IC2") (pin "9") (pinfunction "GPOUT5_9") (pintype "output"))
    )
    (net (code "27") (name "/GPOUT6") (class "Default")
      (node (ref "GO6") (pin "1") (pinfunction "1_1") (pintype "passive"))
      (node (ref "IC2") (pin "10") (pinfunction "GPOUT6_10") (pintype "output"))
    )
    (net (code "28") (name "/GPOUT7") (class "Default")
      (node (ref "GO7") (pin "1") (pinfunction "1_1") (pintype "passive"))
      (node (ref "IC2") (pin "11") (pinfunction "GPOUT7_11") (pintype "output"))
    )
    (net (code "29") (name "/GPX") (class "Default")
      (node (ref "GPX") (pin "1") (pinfunction "1_1") (pintype "passive"))
      (node (ref "IC2") (pin "17") (pinfunction "GPX_17") (pintype "output"))
      (node (ref "U1") (pin "4") (pinfunction "EN_4") (pintype "bidirectional"))
    )
    (net (code "30") (name "/LED") (class "Default")
      (node (ref "IC1") (pin "44") (pinfunction "(PCINT12/OC0B/~{SS})PB4_44") (pintype "bidirectional"))
      (node (ref "R10") (pin "2") (pinfunction "2_2") (pintype "passive"))
      (node (ref "SV2") (pin "10") (pinfunction "10_10") (pintype "passive"))
    )
    (net (code "31") (name "/M1A") (class "Default")
      (node (ref "IC1") (pin "25") (pinfunction "(PCINT22/TOSC1)PC6_25") (pintype "output"))
      (node (ref "M1A") (pin "1") (pinfunction "1_1") (pintype "passive"))
      (node (ref "R20") (pin "2") (pinfunction "2_2") (pintype "passive"))
      (node (ref "R41") (pin "2") (pinfunction "2_2") (pintype "passive"))
    )
    (net (code "32") (name "/M1B") (class "Default")
      (node (ref "IC1") (pin "26") (pinfunction "(PCINT23/TOSC2)PC7_26") (pintype "output"))
      (node (ref "M1B") (pin "1") (pinfunction "1_1") (pintype "passive"))
      (node (ref "R21") (pin "2") (pinfunction "2_2") (pintype "passive"))
      (node (ref "R40") (pin "2") (pinfunction "2_2") (pintype "passive"))
    )
    (net (code "33") (name "/M1CS") (class "Default")
      (node (ref "C14") (pin "1") (pinfunction "1_1") (pintype "passive"))
      (node (ref "R18") (pin "1") (pinfunction "1_1") (pintype "passive"))
      (node (ref "SV4") (pin "1") (pinfunction "1_1") (pintype "passive"))
    )
    (net (code "34") (name "/M1CS_DIS") (class "Default")
      (node (ref "R14") (pin "1") (pinfunction "1_1") (pintype "passive"))
      (node (ref "SV4") (pin "2") (pinfunction "2_2") (pintype "passive"))
    )
    (net (code "35") (name "/M1EN") (class "Default")
      (node (ref "IC1") (pin "23") (pinfunction "(PCINT20/TDO)PC4_23") (pintype "output"))
      (node (ref "M1EN") (pin "1") (pinfunction "1_1") (pintype "passive"))
      (node (ref "R16") (pin "2") (pinfunction "2_2") (pintype "passive"))
    )
    (net (code "36") (name "/M2A") (class "Default")
      (node (ref "IC1") (pin "42") (pinfunction "(PCINT10/INT2/AIN0)PB2_42") (pintype "bidirectional"))
      (node (ref "M2A") (pin "1") (pinfunction "1_1") (pintype "passive"))
      (node (ref "R27") (pin "2") (pinfunction "2_2") (pintype "passive"))
      (node (ref "R39") (pin "2") (pinfunction "2_2") (pintype "passive"))
    )
    (net (code "37") (name "/M2B") (class "Default")
      (node (ref "IC1") (pin "43") (pinfunction "(PCINT11/OC0A/AIN1)PB3_43") (pintype "bidirectional"))
      (node (ref "M2B") (pin "1") (pinfunction "1_1") (pintype "passive"))
      (node (ref "R28") (pin "2") (pinfunction "2_2") (pintype "passive"))
      (node (ref "R38") (pin "2") (pinfunction "2_2") (pintype "passive"))
    )
    (net (code "38") (name "/M2CS") (class "Default")
      (node (ref "C27") (pin "1") (pinfunction "1_1") (pintype "passive"))
      (node (ref "R25") (pin "1") (pinfunction "1_1") (pintype "passive"))
      (node (ref "SV5") (pin "1") (pinfunction "1_1") (pintype "passive"))
    )
    (net (code "39") (name "/M2CS_DIS") (class "Default")
      (node (ref "R29") (pin "1") (pinfunction "1_1") (pintype "passive"))
      (node (ref "SV5") (pin "2") (pinfunction "2_2") (pintype "passive"))
    )
    (net (code "40") (name "/M2EN") (class "Default")
      (node (ref "IC1") (pin "24") (pinfunction "(PCINT21/TDI)PC5_24") (pintype "output"))
      (node (ref "M2EN") (pin "1") (pinfunction "1_1") (pintype "passive"))
      (node (ref "R23") (pin "2") (pinfunction "2_2") (pintype "passive"))
    )
    (net (code "41") (name "/MAX_INT") (class "Default")
      (node (ref "IC1") (pin "21") (pinfunction "(PCINT18/TCK)PC2_21") (pintype "output"))
      (node (ref "IC2") (pin "18") (pinfunction "INT_18") (pintype "output"))
      (node (ref "R5") (pin "1") (pinfunction "1_1") (pintype "passive"))
    )
    (net (code "42") (name "/MAX_SS") (class "Default")
      (node (ref "IC1") (pin "22") (pinfunction "(PCINT19/TMS)PC3_22") (pintype "output"))
      (node (ref "IC2") (pin "14") (pinfunction "SS_14") (pintype "input"))
      (node (ref "R37") (pin "2") (pinfunction "2_2") (pintype "passive"))
    )
    (net (code "43") (name "/MISO") (class "Default")
      (node (ref "IC1") (pin "2") (pinfunction "(PCINT14/MISO)PB6_2") (pintype "bidirectional"))
      (node (ref "IC2") (pin "15") (pinfunction "MISO_15") (pintype "output"))
      (node (ref "X3") (pin "1") (pinfunction "1_1") (pintype "passive"))
    )
    (net (code "44") (name "/MOSI") (class "Default")
      (node (ref "IC1") (pin "1") (pinfunction "(PCINT13/MOSI)PB5_1") (pintype "bidirectional"))
      (node (ref "IC2") (pin "16") (pinfunction "MOSI_16") (pintype "input"))
      (node (ref "X3") (pin "4") (pinfunction "4_4") (pintype "passive"))
    )
    (net (code "45") (name "/MOUT1A") (class "Default")
      (node (ref "IC5") (pin "10") (pinfunction "SOURCE_HSA1_10") (pintype "bidirectional"))
      (node (ref "IC5") (pin "11") (pinfunction "SOURCE_HSA2_11") (pintype "bidirectional"))
      (node (ref "IC5") (pin "12") (pinfunction "SOURCE_HSA3_12") (pintype "bidirectional"))
      (node (ref "IC5") (pin "2") (pinfunction "DRAIN_LSA1_2") (pintype "bidirectional"))
      (node (ref "IC5") (pin "8") (pinfunction "DRAIN_LSA2_8") (pintype "bidirectional"))
      (node (ref "IC5") (pin "S2") (pinfunction "DRAIN_LSA3_S2") (pintype "bidirectional"))
      (node (ref "MOTOR1") (pin "1") (pinfunction "S_1") (pintype "passive"))
    )
    (net (code "46") (name "/MOUT1B") (class "Default")
      (node (ref "IC5") (pin "25") (pinfunction "SOURCE_HSB1_25") (pintype "bidirectional"))
      (node (ref "IC5") (pin "26") (pinfunction "SOURCE_HSB2_26") (pintype "bidirectional"))
      (node (ref "IC5") (pin "27") (pinfunction "SOURCE_HSB3_27") (pintype "bidirectional"))
      (node (ref "IC5") (pin "29") (pinfunction "DRAIN_LSB1_29") (pintype "bidirectional"))
      (node (ref "IC5") (pin "35") (pinfunction "DRAIN_LSB2_35") (pintype "bidirectional"))
      (node (ref "IC5") (pin "S3") (pinfunction "DRAIN_LSB3_S3") (pintype "bidirectional"))
      (node (ref "MOTOR1") (pin "2") (pinfunction "S_2") (pintype "passive"))
    )
    (net (code "47") (name "/MOUT2A") (class "Default")
      (node (ref "IC6") (pin "10") (pinfunction "SOURCE_HSA1_10") (pintype "bidirectional"))
      (node (ref "IC6") (pin "11") (pinfunction "SOURCE_HSA2_11") (pintype "bidirectional"))
      (node (ref "IC6") (pin "12") (pinfunction "SOURCE_HSA3_12") (pintype "bidirectional"))
      (node (ref "IC6") (pin "2") (pinfunction "DRAIN_LSA1_2") (pintype "bidirectional"))
      (node (ref "IC6") (pin "8") (pinfunction "DRAIN_LSA2_8") (pintype "bidirectional"))
      (node (ref "IC6") (pin "S2") (pinfunction "DRAIN_LSA3_S2") (pintype "bidirectional"))
      (node (ref "MOTOR2") (pin "1") (pinfunction "S_1") (pintype "passive"))
    )
    (net (code "48") (name "/MOUT2B") (class "Default")
      (node (ref "IC6") (pin "25") (pinfunction "SOURCE_HSB1_25") (pintype "bidirectional"))
      (node (ref "IC6") (pin "26") (pinfunction "SOURCE_HSB2_26") (pintype "bidirectional"))
      (node (ref "IC6") (pin "27") (pinfunction "SOURCE_HSB3_27") (pintype "bidirectional"))
      (node (ref "IC6") (pin "29") (pinfunction "DRAIN_LSB1_29") (pintype "bidirectional"))
      (node (ref "IC6") (pin "35") (pinfunction "DRAIN_LSB2_35") (pintype "bidirectional"))
      (node (ref "IC6") (pin "S3") (pinfunction "DRAIN_LSB3_S3") (pintype "bidirectional"))
      (node (ref "MOTOR2") (pin "2") (pinfunction "S_2") (pintype "passive"))
    )
    (net (code "49") (name "/PWM1A") (class "Default")
      (node (ref "IC1") (pin "14") (pinfunction "(PCINT29/OC1A)PD5_14") (pintype "bidirectional"))
      (node (ref "PWM1A") (pin "1") (pinfunction "1_1") (pintype "passive"))
      (node (ref "R19") (pin "2") (pinfunction "2_2") (pintype "passive"))
    )
    (net (code "50") (name "/PWM1B") (class "Default")
      (node (ref "IC1") (pin "13") (pinfunction "(PCINT28/OC1B)PD4_13") (pintype "bidirectional"))
      (node (ref "PWM1B") (pin "1") (pinfunction "1_1") (pintype "passive"))
      (node (ref "R26") (pin "2") (pinfunction "2_2") (pintype "passive"))
    )
    (net (code "51") (name "/PWM2A") (class "Default")
      (node (ref "IC1") (pin "16") (pinfunction "(PCINT31/OC2A)PD7_16") (pintype "bidirectional"))
      (node (ref "SV2") (pin "9") (pinfunction "9_9") (pintype "passive"))
    )
    (net (code "52") (name "/PWM2B") (class "Default")
      (node (ref "IC1") (pin "15") (pinfunction "(PCINT30/OC2B/ICP)PD6_15") (pintype "bidirectional"))
      (node (ref "SV2") (pin "8") (pinfunction "8_8") (pintype "passive"))
    )
    (net (code "53") (name "/RESET") (class "Default")
      (node (ref "D3") (pin "A") (pinfunction "A_A") (pintype "passive"))
      (node (ref "IC1") (pin "4") (pinfunction "RESET_4") (pintype "input"))
      (node (ref "IC2") (pin "12") (pinfunction "~{RESET}_12") (pintype "input"))
      (node (ref "R1") (pin "1") (pinfunction "1_1") (pintype "passive"))
      (node (ref "RESET_EN") (pin "2") (pinfunction "2_2") (pintype "passive"))
      (node (ref "S1") (pin "B2") (pinfunction "2_B2") (pintype "passive"))
      (node (ref "SV2") (pin "3") (pinfunction "3_3") (pintype "passive"))
      (node (ref "X3") (pin "5") (pinfunction "5_5") (pintype "passive"))
    )
    (net (code "54") (name "/RTS") (class "Default")
      (node (ref "C3") (pin "1") (pinfunction "1_1") (pintype "passive"))
      (node (ref "IC9") (pin "16") (pinfunction "~{RTS}_16") (pintype "output"))
    )
    (net (code "55") (name "/RXD0") (class "Default")
      (node (ref "IC1") (pin "9") (pinfunction "(PCINT24/RXD0)PD0_9") (pintype "bidirectional"))
      (node (ref "R8") (pin "1") (pinfunction "1_1") (pintype "passive"))
      (node (ref "SV2") (pin "4") (pinfunction "4_4") (pintype "passive"))
    )
    (net (code "56") (name "/RXD1") (class "Default")
      (node (ref "IC1") (pin "11") (pinfunction "(PCINT26/INT0)PD2_11") (pintype "bidirectional"))
      (node (ref "SV2") (pin "6") (pinfunction "6_6") (pintype "passive"))
    )
    (net (code "57") (name "/RXLED") (class "Default")
      (node (ref "IC9") (pin "11") (pinfunction "CBUS1_11") (pintype "bidirectional"))
      (node (ref "RX") (pin "C") (pinfunction "C_C") (pintype "passive"))
    )
    (net (code "58") (name "/SCK") (class "Default")
      (node (ref "IC1") (pin "3") (pinfunction "(PCINT15/SCK)PB7_3") (pintype "bidirectional"))
      (node (ref "IC2") (pin "13") (pinfunction "SCLK_13") (pintype "input"))
      (node (ref "X3") (pin "3") (pinfunction "3_3") (pintype "passive"))
    )
    (net (code "59") (name "/SCL") (class "Default")
      (node (ref "IC1") (pin "19") (pinfunction "(PCINT16/SCL)PC0_19") (pintype "output"))
      (node (ref "IC3") (pin "23") (pinfunction "SCL_23") (pintype "bidirectional"))
      (node (ref "R30") (pin "1") (pinfunction "1_1") (pintype "passive"))
      (node (ref "SV1") (pin "10") (pinfunction "10_10") (pintype "passive"))
    )
    (net (code "60") (name "/SDA") (class "Default")
      (node (ref "IC1") (pin "20") (pinfunction "(PCINT17/SDA)PC1_20") (pintype "output"))
      (node (ref "IC3") (pin "24") (pinfunction "SDA_24") (pintype "bidirectional"))
      (node (ref "R31") (pin "1") (pinfunction "1_1") (pintype "passive"))
      (node (ref "SV1") (pin "9") (pinfunction "9_9") (pintype "passive"))
    )
    (net (code "61") (name "/TXD0") (class "Default")
      (node (ref "IC1") (pin "10") (pinfunction "(PCINT25/TXD0)PD1_10") (pintype "bidirectional"))
      (node (ref "R9") (pin "1") (pinfunction "1_1") (pintype "passive"))
      (node (ref "SV2") (pin "5") (pinfunction "5_5") (pintype "passive"))
    )
    (net (code "62") (name "/TXD1") (class "Default")
      (node (ref "IC1") (pin "12") (pinfunction "(PCINT27/INT1)PD3_12") (pintype "bidirectional"))
      (node (ref "SV2") (pin "7") (pinfunction "7_7") (pintype "passive"))
    )
    (net (code "63") (name "/TXLED") (class "Default")
      (node (ref "IC9") (pin "5") (pinfunction "CBUS2_5") (pintype "bidirectional"))
      (node (ref "TX") (pin "C") (pinfunction "C_C") (pintype "passive"))
    )
    (net (code "64") (name "/VBAT") (class "Default")
      (node (ref "C34") (pin "2") (pinfunction "2_2") (pintype "passive"))
      (node (ref "IC1") (pin "32") (pinfunction "(PCINT5/ADC5)PA5_32") (pintype "bidirectional"))
      (node (ref "R35") (pin "1") (pinfunction "1_1") (pintype "passive"))
      (node (ref "R36") (pin "2") (pinfunction "2_2") (pintype "passive"))
    )
    (net (code "65") (name "/VBUS") (class "Default")
      (node (ref "C12") (pin "1") (pinfunction "1_1") (pintype "passive"))
      (node (ref "C13") (pin "2") (pinfunction "2_2") (pintype "passive"))
      (node (ref "D1") (pin "A") (pinfunction "A_A") (pintype "passive"))
      (node (ref "F2") (pin "2") (pinfunction "2_2") (pintype "bidirectional"))
      (node (ref "IC9") (pin "10") (pinfunction "VCC_10") (pintype "power_in"))
      (node (ref "R3") (pin "2") (pinfunction "2_2") (pintype "passive"))
      (node (ref "R4") (pin "2") (pinfunction "2_2") (pintype "passive"))
    )
    (net (code "66") (name "/VBUS_HOST") (class "Default")
      (node (ref "C18") (pin "1") (pinfunction "1_1") (pintype "passive"))
      (node (ref "C19") (pin "1") (pinfunction "1_1") (pintype "passive"))
      (node (ref "U1") (pin "1") (pinfunction "OUT_1") (pintype "bidirectional"))
      (node (ref "X5") (pin "1") (pinfunction "1_1") (pintype "passive"))
    )
    (net (code "67") (name "GND") (class "Default")
      (node (ref "C1") (pin "1") (pinfunction "1_1") (pintype "passive"))
      (node (ref "C10") (pin "2") (pinfunction "2_2") (pintype "passive"))
      (node (ref "C11") (pin "-") (pinfunction "-_-") (pintype "passive"))
      (node (ref "C12") (pin "2") (pinfunction "2_2") (pintype "passive"))
      (node (ref "C13") (pin "1") (pinfunction "1_1") (pintype "passive"))
      (node (ref "C14") (pin "2") (pinfunction "2_2") (pintype "passive"))
      (node (ref "C15") (pin "2") (pinfunction "2_2") (pintype "passive"))
      (node (ref "C16") (pin "1") (pinfunction "1_1") (pintype "passive"))
      (node (ref "C17") (pin "1") (pinfunction "1_1") (pintype "passive"))
      (node (ref "C18") (pin "2") (pinfunction "2_2") (pintype "passive"))
      (node (ref "C19") (pin "2") (pinfunction "2_2") (pintype "passive"))
      (node (ref "C2") (pin "2") (pinfunction "2_2") (pintype "passive"))
      (node (ref "C20") (pin "-") (pinfunction "-_-") (pintype "passive"))
      (node (ref "C21") (pin "2") (pinfunction "2_2") (pintype "passive"))
      (node (ref "C22") (pin "2") (pinfunction "2_2") (pintype "passive"))
      (node (ref "C23") (pin "1") (pinfunction "1_1") (pintype "passive"))
      (node (ref "C24") (pin "1") (pinfunction "1_1") (pintype "passive"))
      (node (ref "C25") (pin "2") (pinfunction "2_2") (pintype "passive"))
      (node (ref "C26") (pin "1") (pinfunction "1_1") (pintype "passive"))
      (node (ref "C27") (pin "2") (pinfunction "2_2") (pintype "passive"))
      (node (ref "C28") (pin "1") (pinfunction "1_1") (pintype "passive"))
      (node (ref "C29") (pin "1") (pinfunction "1_1") (pintype "passive"))
      (node (ref "C30") (pin "1") (pinfunction "1_1") (pintype "passive"))
      (node (ref "C31") (pin "1") (pinfunction "1_1") (pintype "passive"))
      (node (ref "C32") (pin "2") (pinfunction "2_2") (pintype "passive"))
      (node (ref "C33") (pin "-") (pinfunction "-_-") (pintype "passive"))
      (node (ref "C34") (pin "1") (pinfunction "1_1") (pintype "passive"))
      (node (ref "C36") (pin "1") (pinfunction "1_1") (pintype "passive"))
      (node (ref "C37") (pin "2") (pinfunction "2_2") (pintype "passive"))
      (node (ref "C4") (pin "1") (pinfunction "1_1") (pintype "passive"))
      (node (ref "C5") (pin "2") (pinfunction "2_2") (pintype "passive"))
      (node (ref "C6") (pin "1") (pinfunction "1_1") (pintype "passive"))
      (node (ref "C7") (pin "2") (pinfunction "2_2") (pintype "passive"))
      (node (ref "C8") (pin "-") (pinfunction "-_-") (pintype "passive"))
      (node (ref "C9") (pin "1") (pinfunction "1_1") (pintype "passive"))
      (node (ref "IC1") (pin "18") (pinfunction "GND_18") (pintype "power_in"))
      (node (ref "IC1") (pin "28") (pinfunction "GND_28") (pintype "power_in"))
      (node (ref "IC1") (pin "39") (pinfunction "GND_39") (pintype "power_in"))
      (node (ref "IC1") (pin "6") (pinfunction "GND_6") (pintype "power_in"))
      (node (ref "IC2") (pin "19") (pinfunction "GND_19") (pintype "power_in"))
      (node (ref "IC2") (pin "3") (pinfunction "GND_3") (pintype "power_in"))
      (node (ref "IC3") (pin "1") (pinfunction "CLKIN_1") (pintype "bidirectional"))
      (node (ref "IC3") (pin "11") (pinfunction "FSYNC_11") (pintype "bidirectional"))
      (node (ref "IC3") (pin "18") (pinfunction "GND_18") (pintype "bidirectional"))
      (node (ref "IC3") (pin "9") (pinfunction "AD0_9") (pintype "bidirectional"))
      (node (ref "IC4") (pin "1") (pinfunction "ADJ_1") (pintype "input"))
      (node (ref "IC5") (pin "3") (pinfunction "GND_A1_3") (pintype "power_in"))
      (node (ref "IC5") (pin "30") (pinfunction "GND_B1_30") (pintype "power_in"))
      (node (ref "IC5") (pin "31") (pinfunction "GND_B2_31") (pintype "power_in"))
      (node (ref "IC5") (pin "33") (pinfunction "GND_B3_33") (pintype "power_in"))
      (node (ref "IC5") (pin "34") (pinfunction "GND_B4_34") (pintype "power_in"))
      (node (ref "IC5") (pin "4") (pinfunction "GND_A2_4") (pintype "power_in"))
      (node (ref "IC5") (pin "6") (pinfunction "GND_A3_6") (pintype "power_in"))
      (node (ref "IC5") (pin "7") (pinfunction "GND_A4_7") (pintype "power_in"))
      (node (ref "IC6") (pin "3") (pinfunction "GND_A1_3") (pintype "power_in"))
      (node (ref "IC6") (pin "30") (pinfunction "GND_B1_30") (pintype "power_in"))
      (node (ref "IC6") (pin "31") (pinfunction "GND_B2_31") (pintype "power_in"))
      (node (ref "IC6") (pin "33") (pinfunction "GND_B3_33") (pintype "power_in"))
      (node (ref "IC6") (pin "34") (pinfunction "GND_B4_34") (pintype "power_in"))
      (node (ref "IC6") (pin "4") (pinfunction "GND_A2_4") (pintype "power_in"))
      (node (ref "IC6") (pin "6") (pinfunction "GND_A3_6") (pintype "power_in"))
      (node (ref "IC6") (pin "7") (pinfunction "GND_A4_7") (pintype "power_in"))
      (node (ref "IC8") (pin "1") (pinfunction "GND_1") (pintype "input"))
      (node (ref "IC9") (pin "13") (pinfunction "GND_13") (pintype "power_in"))
      (node (ref "IC9") (pin "3") (pinfunction "GND_3") (pintype "power_in"))
      (node (ref "IC9") (pin "4") (pinfunction "~{CTS}_4") (pintype "input"))
      (node (ref "LED") (pin "C") (pinfunction "C_C") (pintype "passive"))
      (node (ref "MOTOR1") (pin "3") (pinfunction "S_3") (pintype "passive"))
      (node (ref "MOTOR2") (pin "3") (pinfunction "S_3") (pintype "passive"))
      (node (ref "PWR") (pin "C") (pinfunction "C_C") (pintype "passive"))
      (node (ref "Q3") (pin "1") (pinfunction "G_1") (pintype "passive"))
      (node (ref "Q4") (pin "2") (pinfunction "E_2") (pintype "passive"))
      (node (ref "R17") (pin "1") (pinfunction "1_1") (pintype "passive"))
      (node (ref "R24") (pin "1") (pinfunction "1_1") (pintype "passive"))
      (node (ref "R36") (pin "1") (pinfunction "1_1") (pintype "passive"))
      (node (ref "R38") (pin "1") (pinfunction "1_1") (pintype "passive"))
      (node (ref "R39") (pin "1") (pinfunction "1_1") (pintype "passive"))
      (node (ref "R40") (pin "1") (pinfunction "1_1") (pintype "passive"))
      (node (ref "R41") (pin "1") (pinfunction "1_1") (pintype "passive"))
      (node (ref "S1") (pin "A2") (pinfunction "1_A2") (pintype "passive"))
      (node (ref "SV1") (pin "2") (pinfunction "2_2") (pintype "passive"))
      (node (ref "SV2") (pin "2") (pinfunction "2_2") (pintype "passive"))
      (node (ref "U1") (pin "2") (pinfunction "GND_2") (pintype "bidirectional"))
      (node (ref "X1") (pin "2") (pinfunction "KL_2") (pintype "passive"))
      (node (ref "X3") (pin "6") (pinfunction "6_6") (pintype "passive"))
      (node (ref "X4") (pin "4") (pinfunction "4_4") (pintype "passive"))
      (node (ref "X4") (pin "S1") (pinfunction "S1_S1") (pintype "passive"))
      (node (ref "X4") (pin "S2") (pinfunction "S2_S2") (pintype "passive"))
      (node (ref "X5") (pin "4") (pinfunction "4_4") (pintype "passive"))
      (node (ref "X5") (pin "S1") (pinfunction "S1_S1") (pintype "passive"))
      (node (ref "X5") (pin "S2") (pinfunction "S2_S2") (pintype "passive"))
    )
    (net (code "68") (name "Net-(C3-Pad2)") (class "Default")
      (node (ref "C3") (pin "2") (pinfunction "2_2") (pintype "passive"))
      (node (ref "RESET_EN") (pin "1") (pinfunction "1_1") (pintype "passive"))
    )
    (net (code "69") (name "Net-(F2-Pad1)") (class "Default")
      (node (ref "F2") (pin "1") (pinfunction "1_1") (pintype "bidirectional"))
      (node (ref "X4") (pin "1") (pinfunction "1_1") (pintype "passive"))
    )
    (net (code "70") (name "Net-(IC1-XTAL1)") (class "Default")
      (node (ref "C2") (pin "1") (pinfunction "1_1") (pintype "passive"))
      (node (ref "IC1") (pin "8") (pinfunction "XTAL1_8") (pintype "bidirectional"))
      (node (ref "Q1") (pin "1") (pinfunction "1_1") (pintype "passive"))
    )
    (net (code "71") (name "Net-(IC1-XTAL2)") (class "Default")
      (node (ref "C1") (pin "2") (pinfunction "2_2") (pintype "passive"))
      (node (ref "IC1") (pin "7") (pinfunction "XTAL2_7") (pintype "bidirectional"))
      (node (ref "Q1") (pin "2") (pinfunction "2_2") (pintype "passive"))
    )
    (net (code "72") (name "Net-(IC2-D+)") (class "Default")
      (node (ref "IC2") (pin "21") (pinfunction "D+_21") (pintype "bidirectional"))
      (node (ref "R6") (pin "2") (pinfunction "2_2") (pintype "passive"))
    )
    (net (code "73") (name "Net-(IC2-D-)") (class "Default")
      (node (ref "IC2") (pin "20") (pinfunction "D-_20") (pintype "bidirectional"))
      (node (ref "R7") (pin "2") (pinfunction "2_2") (pintype "passive"))
    )
    (net (code "74") (name "Net-(IC2-XI)") (class "Default")
      (node (ref "C16") (pin "2") (pinfunction "2_2") (pintype "passive"))
      (node (ref "IC2") (pin "24") (pinfunction "XI_24") (pintype "input"))
      (node (ref "Q2") (pin "1") (pinfunction "1_1") (pintype "passive"))
    )
    (net (code "75") (name "Net-(IC2-XO)") (class "Default")
      (node (ref "C17") (pin "2") (pinfunction "2_2") (pintype "passive"))
      (node (ref "IC2") (pin "25") (pinfunction "XO_25") (pintype "output"))
      (node (ref "Q2") (pin "2") (pinfunction "2_2") (pintype "passive"))
    )
    (net (code "76") (name "Net-(IC3-CPOUT)") (class "Default")
      (node (ref "C22") (pin "1") (pinfunction "1_1") (pintype "passive"))
      (node (ref "IC3") (pin "20") (pinfunction "CPOUT_20") (pintype "bidirectional"))
    )
    (net (code "77") (name "Net-(IC3-INT)") (class "Default")
      (node (ref "IC3") (pin "12") (pinfunction "INT_12") (pintype "bidirectional"))
      (node (ref "INT") (pin "1") (pinfunction "1_1") (pintype "passive"))
    )
    (net (code "78") (name "Net-(IC3-REGOUT)") (class "Default")
      (node (ref "C23") (pin "2") (pinfunction "2_2") (pintype "passive"))
      (node (ref "IC3") (pin "10") (pinfunction "REGOUT_10") (pintype "bidirectional"))
    )
    (net (code "79") (name "Net-(IC5-CS)") (class "Default")
      (node (ref "IC5") (pin "19") (pinfunction "CS_19") (pintype "output"))
      (node (ref "R17") (pin "2") (pinfunction "2_2") (pintype "passive"))
      (node (ref "R18") (pin "2") (pinfunction "2_2") (pintype "passive"))
    )
    (net (code "80") (name "Net-(IC5-CS_DIS)") (class "Default")
      (node (ref "IC5") (pin "20") (pinfunction "CS_DIS_20") (pintype "input"))
      (node (ref "R12") (pin "1") (pinfunction "1_1") (pintype "passive"))
      (node (ref "R14") (pin "2") (pinfunction "2_2") (pintype "passive"))
    )
    (net (code "81") (name "Net-(IC5-EN{slash}DIAG_A)") (class "Default")
      (node (ref "IC5") (pin "16") (pinfunction "EN/DIAG_A_16") (pintype "input"))
      (node (ref "IC5") (pin "21") (pinfunction "EN/DIAG_B_21") (pintype "input"))
      (node (ref "R15") (pin "1") (pinfunction "1_1") (pintype "passive"))
      (node (ref "R16") (pin "1") (pinfunction "1_1") (pintype "passive"))
    )
    (net (code "82") (name "Net-(IC5-IN_A)") (class "Default")
      (node (ref "IC5") (pin "15") (pinfunction "IN_A_15") (pintype "input"))
      (node (ref "R20") (pin "1") (pinfunction "1_1") (pintype "passive"))
    )
    (net (code "83") (name "Net-(IC5-IN_B)") (class "Default")
      (node (ref "IC5") (pin "22") (pinfunction "IN_B_22") (pintype "input"))
      (node (ref "R21") (pin "1") (pinfunction "1_1") (pintype "passive"))
    )
    (net (code "84") (name "Net-(IC5-IN_PWM)") (class "Default")
      (node (ref "IC5") (pin "17") (pinfunction "IN_PWM_17") (pintype "input"))
      (node (ref "R19") (pin "1") (pinfunction "1_1") (pintype "passive"))
    )
    (net (code "85") (name "Net-(IC6-CS)") (class "Default")
      (node (ref "IC6") (pin "19") (pinfunction "CS_19") (pintype "output"))
      (node (ref "R24") (pin "2") (pinfunction "2_2") (pintype "passive"))
      (node (ref "R25") (pin "2") (pinfunction "2_2") (pintype "passive"))
    )
    (net (code "86") (name "Net-(IC6-CS_DIS)") (class "Default")
      (node (ref "IC6") (pin "20") (pinfunction "CS_DIS_20") (pintype "input"))
      (node (ref "R22") (pin "1") (pinfunction "1_1") (pintype "passive"))
      (node (ref "R29") (pin "2") (pinfunction "2_2") (pintype "passive"))
    )
    (net (code "87") (name "Net-(IC6-EN{slash}DIAG_A)") (class "Default")
      (node (ref "IC6") (pin "16") (pinfunction "EN/DIAG_A_16") (pintype "input"))
      (node (ref "IC6") (pin "21") (pinfunction "EN/DIAG_B_21") (pintype "input"))
      (node (ref "R13") (pin "1") (pinfunction "1_1") (pintype "passive"))
      (node (ref "R23") (pin "1") (pinfunction "1_1") (pintype "passive"))
    )
    (net (code "88") (name "Net-(IC6-IN_A)") (class "Default")
      (node (ref "IC6") (pin "15") (pinfunction "IN_A_15") (pintype "input"))
      (node (ref "R27") (pin "1") (pinfunction "1_1") (pintype "passive"))
    )
    (net (code "89") (name "Net-(IC6-IN_B)") (class "Default")
      (node (ref "IC6") (pin "22") (pinfunction "IN_B_22") (pintype "input"))
      (node (ref "R28") (pin "1") (pinfunction "1_1") (pintype "passive"))
    )
    (net (code "90") (name "Net-(IC6-IN_PWM)") (class "Default")
      (node (ref "IC6") (pin "17") (pinfunction "IN_PWM_17") (pintype "input"))
      (node (ref "R26") (pin "1") (pinfunction "1_1") (pintype "passive"))
    )
    (net (code "91") (name "Net-(IC9-3V3OUT)") (class "Default")
      (node (ref "C30") (pin "2") (pinfunction "2_2") (pintype "passive"))
      (node (ref "IC9") (pin "8") (pinfunction "3V3OUT_8") (pintype "output"))
      (node (ref "IC9") (pin "9") (pinfunction "~{RESET}_9") (pintype "input"))
    )
    (net (code "92") (name "Net-(IC9-RXD)") (class "Default")
      (node (ref "IC9") (pin "2") (pinfunction "RXD_2") (pintype "input"))
      (node (ref "R9") (pin "2") (pinfunction "2_2") (pintype "passive"))
    )
    (net (code "93") (name "Net-(IC9-TXD)") (class "Default")
      (node (ref "IC9") (pin "15") (pinfunction "TXD_15") (pintype "output"))
      (node (ref "R8") (pin "2") (pinfunction "2_2") (pintype "passive"))
    )
    (net (code "94") (name "Net-(IC9-USBDM)") (class "Default")
      (node (ref "IC9") (pin "7") (pinfunction "USBDM_7") (pintype "input"))
      (node (ref "R33") (pin "2") (pinfunction "2_2") (pintype "passive"))
    )
    (net (code "95") (name "Net-(IC9-USBDP)") (class "Default")
      (node (ref "IC9") (pin "6") (pinfunction "USBDP_6") (pintype "input"))
      (node (ref "R32") (pin "2") (pinfunction "2_2") (pintype "passive"))
    )
    (net (code "96") (name "Net-(JP1-Pad2)") (class "Default")
      (node (ref "JP1") (pin "2") (pinfunction "2_2") (pintype "passive"))
      (node (ref "R11") (pin "1") (pinfunction "1_1") (pintype "passive"))
    )
    (net (code "97") (name "Net-(LED-PadA)") (class "Default")
      (node (ref "LED") (pin "A") (pinfunction "A_A") (pintype "passive"))
      (node (ref "R10") (pin "1") (pinfunction "1_1") (pintype "passive"))
    )
    (net (code "98") (name "Net-(OL-PadA)") (class "Default")
      (node (ref "OL") (pin "A") (pinfunction "A_A") (pintype "passive"))
      (node (ref "R42") (pin "1") (pinfunction "1_1") (pintype "passive"))
    )
    (net (code "99") (name "Net-(PWR-PadA)") (class "Default")
      (node (ref "PWR") (pin "A") (pinfunction "A_A") (pintype "passive"))
      (node (ref "R2") (pin "1") (pinfunction "1_1") (pintype "passive"))
    )
    (net (code "100") (name "Net-(Q4-B)") (class "Default")
      (node (ref "Q4") (pin "1") (pinfunction "B_1") (pintype "passive"))
      (node (ref "R11") (pin "2") (pinfunction "2_2") (pintype "passive"))
    )
    (net (code "101") (name "Net-(Q4-C)") (class "Default")
      (node (ref "D2") (pin "A") (pinfunction "A_A") (pintype "passive"))
      (node (ref "Q4") (pin "3") (pinfunction "C_3") (pintype "passive"))
      (node (ref "SG1") (pin "-") (pinfunction "2_-") (pintype "passive"))
    )
    (net (code "102") (name "Net-(R3-Pad1)") (class "Default")
      (node (ref "R3") (pin "1") (pinfunction "1_1") (pintype "passive"))
      (node (ref "RX") (pin "A") (pinfunction "A_A") (pintype "passive"))
    )
    (net (code "103") (name "Net-(R4-Pad1)") (class "Default")
      (node (ref "R4") (pin "1") (pinfunction "1_1") (pintype "passive"))
      (node (ref "TX") (pin "A") (pinfunction "A_A") (pintype "passive"))
    )
    (net (code "104") (name "Net-(R6-Pad1)") (class "Default")
      (node (ref "R6") (pin "1") (pinfunction "1_1") (pintype "passive"))
      (node (ref "X5") (pin "3") (pinfunction "3_3") (pintype "passive"))
    )
    (net (code "105") (name "Net-(R7-Pad1)") (class "Default")
      (node (ref "R7") (pin "1") (pinfunction "1_1") (pintype "passive"))
      (node (ref "X5") (pin "2") (pinfunction "2_2") (pintype "passive"))
    )
    (net (code "106") (name "Net-(R32-Pad1)") (class "Default")
      (node (ref "R32") (pin "1") (pinfunction "1_1") (pintype "passive"))
      (node (ref "X4") (pin "3") (pinfunction "3_3") (pintype "passive"))
    )
    (net (code "107") (name "Net-(R33-Pad1)") (class "Default")
      (node (ref "R33") (pin "1") (pinfunction "1_1") (pintype "passive"))
      (node (ref "X4") (pin "2") (pinfunction "2_2") (pintype "passive"))
    )
    (net (code "108") (name "Net-(U1-~{FLAG})") (class "Default")
      (node (ref "OL") (pin "C") (pinfunction "C_C") (pintype "passive"))
      (node (ref "U1") (pin "3") (pinfunction "~{FLAG}_3") (pintype "bidirectional"))
    )
    (net (code "109") (name "VCC_BAT") (class "Default")
      (node (ref "C4") (pin "2") (pinfunction "2_2") (pintype "passive"))
      (node (ref "C8") (pin "+") (pinfunction "+_+") (pintype "passive"))
      (node (ref "IC4") (pin "3") (pinfunction "VI_3") (pintype "input"))
      (node (ref "R35") (pin "2") (pinfunction "2_2") (pintype "passive"))
      (node (ref "S4") (pin "1") (pinfunction "S_1") (pintype "passive"))
    )
    (net (code "110") (name "VCC_MOTOR") (class "Default")
      (node (ref "C11") (pin "+") (pinfunction "+_+") (pintype "passive"))
      (node (ref "C20") (pin "+") (pinfunction "+_+") (pintype "passive"))
      (node (ref "C25") (pin "1") (pinfunction "1_1") (pintype "passive"))
      (node (ref "C32") (pin "1") (pinfunction "1_1") (pintype "passive"))
      (node (ref "IC5") (pin "13") (pinfunction "VCC1_13") (pintype "power_in"))
      (node (ref "IC5") (pin "24") (pinfunction "VCC2_24") (pintype "power_in"))
      (node (ref "IC5") (pin "S1") (pinfunction "VCC3_S1") (pintype "power_in"))
      (node (ref "IC6") (pin "13") (pinfunction "VCC1_13") (pintype "power_in"))
      (node (ref "IC6") (pin "24") (pinfunction "VCC2_24") (pintype "power_in"))
      (node (ref "IC6") (pin "S1") (pinfunction "VCC3_S1") (pintype "power_in"))
      (node (ref "Q3") (pin "3") (pinfunction "S_3") (pintype "passive"))
      (node (ref "S4") (pin "2") (pinfunction "P_2") (pintype "passive"))
    )
    (net (code "111") (name "VIN") (class "Default")
      (node (ref "Q3") (pin "4") (pinfunction "D_4") (pintype "passive"))
      (node (ref "SV3") (pin "1") (pinfunction "1_1") (pintype "passive"))
      (node (ref "X1") (pin "1") (pinfunction "KL_1") (pintype "passive"))
    )
    (net (code "112") (name "unconnected-(IC2-VBCOMP-Pad22)") (class "Default")
      (node (ref "IC2") (pin "22") (pinfunction "VBCOMP_22") (pintype "input"))
    )
    (net (code "113") (name "unconnected-(IC3-AUX_CL-Pad7)") (class "Default")
      (node (ref "IC3") (pin "7") (pinfunction "AUX_CL_7") (pintype "bidirectional"))
    )
    (net (code "114") (name "unconnected-(IC3-AUX_DA-Pad6)") (class "Default")
      (node (ref "IC3") (pin "6") (pinfunction "AUX_DA_6") (pintype "bidirectional"))
    )
    (net (code "115") (name "unconnected-(IC5-NC1-Pad1)") (class "Default")
      (node (ref "IC5") (pin "1") (pinfunction "NC1_1") (pintype "no_connect"))
    )
    (net (code "116") (name "unconnected-(IC5-NC2-Pad5)") (class "Default")
      (node (ref "IC5") (pin "5") (pinfunction "NC2_5") (pintype "no_connect"))
    )
    (net (code "117") (name "unconnected-(IC5-NC3-Pad9)") (class "Default")
      (node (ref "IC5") (pin "9") (pinfunction "NC3_9") (pintype "no_connect"))
    )
    (net (code "118") (name "unconnected-(IC5-NC4-Pad14)") (class "Default")
      (node (ref "IC5") (pin "14") (pinfunction "NC4_14") (pintype "no_connect"))
    )
    (net (code "119") (name "unconnected-(IC5-NC5-Pad18)") (class "Default")
      (node (ref "IC5") (pin "18") (pinfunction "NC5_18") (pintype "no_connect"))
    )
    (net (code "120") (name "unconnected-(IC5-NC6-Pad23)") (class "Default")
      (node (ref "IC5") (pin "23") (pinfunction "NC6_23") (pintype "no_connect"))
    )
    (net (code "121") (name "unconnected-(IC5-NC7-Pad28)") (class "Default")
      (node (ref "IC5") (pin "28") (pinfunction "NC7_28") (pintype "no_connect"))
    )
    (net (code "122") (name "unconnected-(IC5-NC8-Pad32)") (class "Default")
      (node (ref "IC5") (pin "32") (pinfunction "NC8_32") (pintype "no_connect"))
    )
    (net (code "123") (name "unconnected-(IC5-NC9-Pad36)") (class "Default")
      (node (ref "IC5") (pin "36") (pinfunction "NC9_36") (pintype "no_connect"))
    )
    (net (code "124") (name "unconnected-(IC6-NC1-Pad1)") (class "Default")
      (node (ref "IC6") (pin "1") (pinfunction "NC1_1") (pintype "no_connect"))
    )
    (net (code "125") (name "unconnected-(IC6-NC2-Pad5)") (class "Default")
      (node (ref "IC6") (pin "5") (pinfunction "NC2_5") (pintype "no_connect"))
    )
    (net (code "126") (name "unconnected-(IC6-NC3-Pad9)") (class "Default")
      (node (ref "IC6") (pin "9") (pinfunction "NC3_9") (pintype "no_connect"))
    )
    (net (code "127") (name "unconnected-(IC6-NC4-Pad14)") (class "Default")
      (node (ref "IC6") (pin "14") (pinfunction "NC4_14") (pintype "no_connect"))
    )
    (net (code "128") (name "unconnected-(IC6-NC5-Pad18)") (class "Default")
      (node (ref "IC6") (pin "18") (pinfunction "NC5_18") (pintype "no_connect"))
    )
    (net (code "129") (name "unconnected-(IC6-NC6-Pad23)") (class "Default")
      (node (ref "IC6") (pin "23") (pinfunction "NC6_23") (pintype "no_connect"))
    )
    (net (code "130") (name "unconnected-(IC6-NC7-Pad28)") (class "Default")
      (node (ref "IC6") (pin "28") (pinfunction "NC7_28") (pintype "no_connect"))
    )
    (net (code "131") (name "unconnected-(IC6-NC8-Pad32)") (class "Default")
      (node (ref "IC6") (pin "32") (pinfunction "NC8_32") (pintype "no_connect"))
    )
    (net (code "132") (name "unconnected-(IC6-NC9-Pad36)") (class "Default")
      (node (ref "IC6") (pin "36") (pinfunction "NC9_36") (pintype "no_connect"))
    )
    (net (code "133") (name "unconnected-(IC9-CBUS0-Pad12)") (class "Default")
      (node (ref "IC9") (pin "12") (pinfunction "CBUS0_12") (pintype "bidirectional"))
    )
    (net (code "134") (name "unconnected-(IC9-CBUS3-Pad14)") (class "Default")
      (node (ref "IC9") (pin "14") (pinfunction "CBUS3_14") (pintype "bidirectional"))
    )
    (net (code "135") (name "unconnected-(S4-O-Pad3)") (class "Default")
      (node (ref "S4") (pin "3") (pinfunction "O_3") (pintype "passive"))
    )
  )
)
